# harp_expander_servo_driver_v1_1.net
KiCad netlist of a schematic drawn in EAGLE
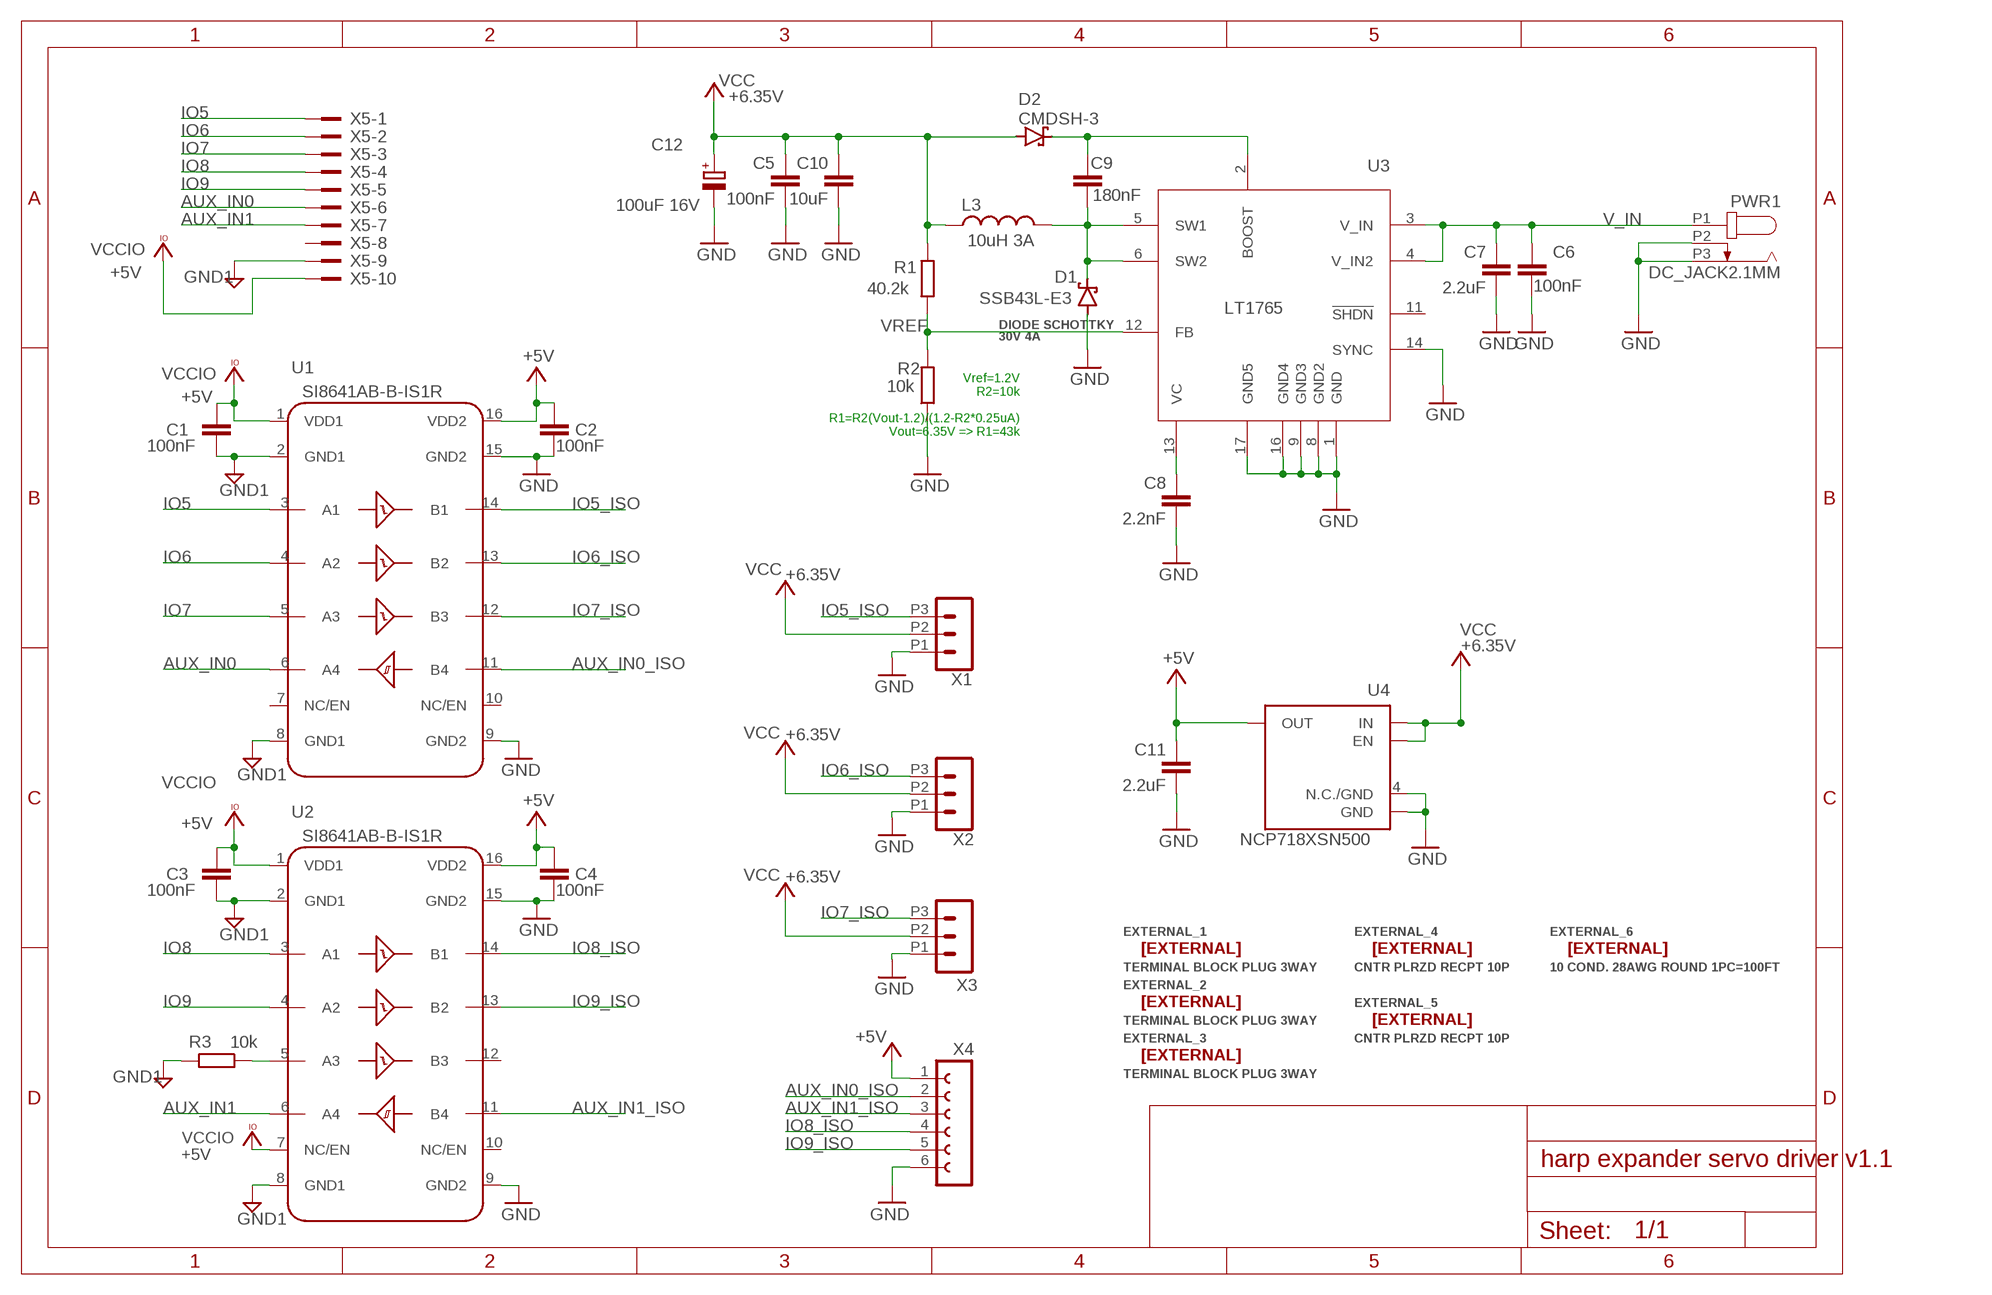
[diagram p0: schematic, sheet 1]

(export (version "E")
  (design (tool "Eeschema 10.0.6"))
  (components
    (comp (ref "C1")
      (value "100nF")
      (footprint "eagle-import:C0402")
      (fields (field (name "MPN") "CGA2B3X7R1H104K050BB"))
      (libsource (lib "eagle-import") (part "C-EUC0402"))
    )
    (comp (ref "C2")
      (value "100nF")
      (footprint "eagle-import:C0402")
      (fields (field (name "MPN") "CGA2B3X7R1H104K050BB"))
      (libsource (lib "eagle-import") (part "C-EUC0402"))
    )
    (comp (ref "C3")
      (value "100nF")
      (footprint "eagle-import:C0402")
      (fields (field (name "MPN") "CGA2B3X7R1H104K050BB"))
      (libsource (lib "eagle-import") (part "C-EUC0402"))
    )
    (comp (ref "C4")
      (value "100nF")
      (footprint "eagle-import:C0402")
      (fields (field (name "MPN") "CGA2B3X7R1H104K050BB"))
      (libsource (lib "eagle-import") (part "C-EUC0402"))
    )
    (comp (ref "C5")
      (value "100nF")
      (footprint "eagle-import:C0402")
      (fields (field (name "MPN") "CGA2B3X7R1H104K050BB"))
      (libsource (lib "eagle-import") (part "C-EUC0402"))
    )
    (comp (ref "C6")
      (value "100nF")
      (footprint "eagle-import:C0402")
      (fields (field (name "MPN") "CGA2B3X7R1H104K050BB"))
      (libsource (lib "eagle-import") (part "C-EUC0402"))
    )
    (comp (ref "C7")
      (value "2.2uF")
      (footprint "eagle-import:C0603")
      (fields (field (name "MPN") "GRM188R61E225MA12D"))
      (libsource (lib "eagle-import") (part "C-EUC0603"))
    )
    (comp (ref "C8")
      (value "2.2nF")
      (footprint "eagle-import:C0402")
      (fields (field (name "MPN") "CL05B222JB5NNNC"))
      (libsource (lib "eagle-import") (part "C-EUC0402"))
    )
    (comp (ref "C9")
      (value "180nF")
      (footprint "eagle-import:C0603")
      (fields (field (name "MPN") "GCG188R91H184KA01D"))
      (libsource (lib "eagle-import") (part "C-EUC0603"))
    )
    (comp (ref "C10")
      (value "10uF")
      (footprint "eagle-import:C0603")
      (fields (field (name "MPN") "EMK107BBJ106MA-T"))
      (libsource (lib "eagle-import") (part "C-EUC0603"))
    )
    (comp (ref "C11")
      (value "2.2uF")
      (footprint "eagle-import:C0603")
      (fields (field (name "MPN") "GRM188R61E225MA12D"))
      (libsource (lib "eagle-import") (part "C-EUC0603"))
    )
    (comp (ref "C12")
      (value "100uF 16V")
      (footprint "eagle-import:CT7343")
      (fields (field (name "MPN") "T491D107K016AT7280"))
      (libsource (lib "eagle-import") (part "CPOL-EUCT7343"))
    )
    (comp (ref "D1")
      (value "SSB43L-E3")
      (footprint "eagle-import:SMB")
      (fields (field (name "MPN") "SSB43L-E3/52T"))
      (libsource (lib "eagle-import") (part "MBRS130LT3"))
    )
    (comp (ref "D2")
      (value "CMDSH-3")
      (footprint "eagle-import:SOD323-R")
      (libsource (lib "eagle-import") (part "SCHOTTKY-DIODESOD323"))
    )
    (comp (ref "EXTERNAL_1")
      (value "TERMINAL BLOCK PLUG 3WAY")
      (footprint "eagle-import:-")
      (fields (field (name "MPN") "691361100003") (field (name "TYPE") "-"))
      (libsource (lib "eagle-import") (part "EXTERNAL"))
    )
    (comp (ref "EXTERNAL_2")
      (value "TERMINAL BLOCK PLUG 3WAY")
      (footprint "eagle-import:-")
      (fields (field (name "MPN") "691361100003") (field (name "TYPE") "-"))
      (libsource (lib "eagle-import") (part "EXTERNAL"))
    )
    (comp (ref "EXTERNAL_3")
      (value "TERMINAL BLOCK PLUG 3WAY")
      (footprint "eagle-import:-")
      (fields (field (name "MPN") "691361100003") (field (name "TYPE") "-"))
      (libsource (lib "eagle-import") (part "EXTERNAL"))
    )
    (comp (ref "EXTERNAL_4")
      (value "CNTR PLRZD RECPT 10P")
      (footprint "eagle-import:-")
      (fields (field (name "MPN") "1658621-1") (field (name "TYPE") "-"))
      (libsource (lib "eagle-import") (part "EXTERNAL"))
    )
    (comp (ref "EXTERNAL_5")
      (value "CNTR PLRZD RECPT 10P")
      (footprint "eagle-import:-")
      (fields (field (name "MPN") "1658621-1") (field (name "TYPE") "-"))
      (libsource (lib "eagle-import") (part "EXTERNAL"))
    )
    (comp (ref "EXTERNAL_6")
      (value "10 COND. 28AWG ROUND 1PC=100FT")
      (footprint "eagle-import:-")
      (fields (field (name "MPN") "3365/10 100") (field (name "TYPE") "-"))
      (libsource (lib "eagle-import") (part "EXTERNAL"))
    )
    (comp (ref "L3")
      (value "10uH 3A")
      (footprint "eagle-import:L_IHLP_PADS")
      (fields (field (name "MPN") "IHLP2525CZER100M01"))
      (libsource (lib "eagle-import") (part "L_IHLP2525CZER100M01"))
    )
    (comp (ref "PWR1")
      (value "DC_JACK2.1MM")
      (footprint "eagle-import:DC_POWER_INPUT_2.1MM")
      (fields (field (name "MPN") "163-179PH-EX"))
      (libsource (lib "eagle-import") (part "DC_JACK2.1MM"))
    )
    (comp (ref "R1")
      (value "40.2k")
      (footprint "eagle-import:R0402")
      (fields (field (name "MPN") "RC0402FR-0740K2L"))
      (libsource (lib "eagle-import") (part "R-EU_R0402"))
    )
    (comp (ref "R2")
      (value "10k")
      (footprint "eagle-import:R0402")
      (fields (field (name "MPN") "CRCW040210K0FKEDC"))
      (libsource (lib "eagle-import") (part "R-EU_R0402"))
    )
    (comp (ref "R3")
      (value "10k")
      (footprint "eagle-import:R0402")
      (fields (field (name "MPN") "CRCW040210K0FKEDC"))
      (libsource (lib "eagle-import") (part "R-EU_R0402"))
    )
    (comp (ref "U1")
      (value "SI8641AB-B-IS1R")
      (footprint "eagle-import:SO16W")
      (libsource (lib "eagle-import") (part "SI8641ABW"))
    )
    (comp (ref "U2")
      (value "SI8641AB-B-IS1R")
      (footprint "eagle-import:SO16W")
      (libsource (lib "eagle-import") (part "SI8641ABW"))
    )
    (comp (ref "U3")
      (value "LT1765")
      (footprint "eagle-import:TSSOP16")
      (fields (field (name "MPN") "LT1765EFE#TRPBF"))
      (libsource (lib "eagle-import") (part "LT1765"))
    )
    (comp (ref "U4")
      (value "NCP718XSN500")
      (footprint "eagle-import:SOT23-5")
      (fields (field (name "MPN") "NCP718BSN500T1G"))
      (libsource (lib "eagle-import") (part "NCP718XSN500"))
    )
    (comp (ref "X1")
      (value "CON_3.5MM_1X3")
      (footprint "eagle-import:CON_3.5MM_1X3")
      (fields (field (name "MPN") "691322110003"))
      (libsource (lib "eagle-import") (part "CON_3.5MM_1X3"))
    )
    (comp (ref "X2")
      (value "CON_3.5MM_1X3")
      (footprint "eagle-import:CON_3.5MM_1X3")
      (fields (field (name "MPN") "691322110003"))
      (libsource (lib "eagle-import") (part "CON_3.5MM_1X3"))
    )
    (comp (ref "X3")
      (value "CON_3.5MM_1X3")
      (footprint "eagle-import:CON_3.5MM_1X3")
      (fields (field (name "MPN") "691322110003"))
      (libsource (lib "eagle-import") (part "CON_3.5MM_1X3"))
    )
    (comp (ref "X4")
      (value "aux_header")
      (footprint "eagle-import:FE06")
      (fields (field (name "MPN") "n.a."))
      (libsource (lib "eagle-import") (part "FE06-1"))
    )
    (comp (ref "X5")
      (value "IDC 10WAY STRAIGHT")
      (footprint "eagle-import:PAK100_2500-10")
      (fields
        (field (name "MF") "3M")
        (field (name "MPN") "2510-6002UB")
        (field (name "DIGIKEY_PN") "S9169-ND")
        (field (name "MF_1") "-")
        (field (name "MPN_1") "SBH11-PBPC-D05-ST-BK")
        (field (name "OC_FARNELL") "-")
        (field (name "OC_NEWARK") "-")
        (field (name "TYPE") "TH")
      )
      (libsource (lib "eagle-import") (part "2510-"))
    )
  )
  (nets
    (net (code "1") (name "+5V") (class "Default")
      (node (ref "C11") (pin "1") (pinfunction "1_1") (pintype "passive"))
      (node (ref "C2") (pin "1") (pinfunction "1_1") (pintype "passive"))
      (node (ref "C4") (pin "1") (pinfunction "1_1") (pintype "passive"))
      (node (ref "U1") (pin "16") (pinfunction "VDD2_16") (pintype "bidirectional"))
      (node (ref "U2") (pin "16") (pinfunction "VDD2_16") (pintype "bidirectional"))
      (node (ref "U4") (pin "5") (pinfunction "OUT_5") (pintype "passive"))
      (node (ref "X4") (pin "1") (pinfunction "1_1") (pintype "passive"))
    )
    (net (code "2") (name "/AUX_IN0") (class "Default")
      (node (ref "U1") (pin "6") (pinfunction "A4_6") (pintype "bidirectional"))
      (node (ref "X5") (pin "6") (pinfunction "KL_6") (pintype "passive"))
    )
    (net (code "3") (name "/AUX_IN0_ISO") (class "Default")
      (node (ref "U1") (pin "11") (pinfunction "B4_11") (pintype "bidirectional"))
      (node (ref "X4") (pin "2") (pinfunction "2_2") (pintype "passive"))
    )
    (net (code "4") (name "/AUX_IN1") (class "Default")
      (node (ref "U2") (pin "6") (pinfunction "A4_6") (pintype "bidirectional"))
      (node (ref "X5") (pin "7") (pinfunction "KL_7") (pintype "passive"))
    )
    (net (code "5") (name "/AUX_IN1_ISO") (class "Default")
      (node (ref "U2") (pin "11") (pinfunction "B4_11") (pintype "bidirectional"))
      (node (ref "X4") (pin "3") (pinfunction "3_3") (pintype "passive"))
    )
    (net (code "6") (name "/IO5") (class "Default")
      (node (ref "U1") (pin "3") (pinfunction "A1_3") (pintype "bidirectional"))
      (node (ref "X5") (pin "1") (pinfunction "KL_1") (pintype "passive"))
    )
    (net (code "7") (name "/IO5_ISO") (class "Default")
      (node (ref "U1") (pin "14") (pinfunction "B1_14") (pintype "bidirectional"))
      (node (ref "X1") (pin "P3") (pinfunction "3_P3") (pintype "passive"))
    )
    (net (code "8") (name "/IO6") (class "Default")
      (node (ref "U1") (pin "4") (pinfunction "A2_4") (pintype "bidirectional"))
      (node (ref "X5") (pin "2") (pinfunction "KL_2") (pintype "passive"))
    )
    (net (code "9") (name "/IO6_ISO") (class "Default")
      (node (ref "U1") (pin "13") (pinfunction "B2_13") (pintype "bidirectional"))
      (node (ref "X2") (pin "P3") (pinfunction "3_P3") (pintype "passive"))
    )
    (net (code "10") (name "/IO7") (class "Default")
      (node (ref "U1") (pin "5") (pinfunction "A3_5") (pintype "bidirectional"))
      (node (ref "X5") (pin "3") (pinfunction "KL_3") (pintype "passive"))
    )
    (net (code "11") (name "/IO7_ISO") (class "Default")
      (node (ref "U1") (pin "12") (pinfunction "B3_12") (pintype "bidirectional"))
      (node (ref "X3") (pin "P3") (pinfunction "3_P3") (pintype "passive"))
    )
    (net (code "12") (name "/IO8") (class "Default")
      (node (ref "U2") (pin "3") (pinfunction "A1_3") (pintype "bidirectional"))
      (node (ref "X5") (pin "4") (pinfunction "KL_4") (pintype "passive"))
    )
    (net (code "13") (name "/IO8_ISO") (class "Default")
      (node (ref "U2") (pin "14") (pinfunction "B1_14") (pintype "bidirectional"))
      (node (ref "X4") (pin "4") (pinfunction "4_4") (pintype "passive"))
    )
    (net (code "14") (name "/IO9") (class "Default")
      (node (ref "U2") (pin "4") (pinfunction "A2_4") (pintype "bidirectional"))
      (node (ref "X5") (pin "5") (pinfunction "KL_5") (pintype "passive"))
    )
    (net (code "15") (name "/IO9_ISO") (class "Default")
      (node (ref "U2") (pin "13") (pinfunction "B2_13") (pintype "bidirectional"))
      (node (ref "X4") (pin "5") (pinfunction "5_5") (pintype "passive"))
    )
    (net (code "16") (name "/VREF") (class "Default")
      (node (ref "R1") (pin "1") (pinfunction "1_1") (pintype "passive"))
      (node (ref "R2") (pin "2") (pinfunction "2_2") (pintype "passive"))
      (node (ref "U3") (pin "12") (pinfunction "FB_12") (pintype "passive"))
    )
    (net (code "17") (name "/V_IN") (class "Default")
      (node (ref "C6") (pin "1") (pinfunction "1_1") (pintype "passive"))
      (node (ref "C7") (pin "1") (pinfunction "1_1") (pintype "passive"))
      (node (ref "PWR1") (pin "P1") (pinfunction "1_P1") (pintype "passive"))
      (node (ref "U3") (pin "3") (pinfunction "V_IN_3") (pintype "passive"))
      (node (ref "U3") (pin "4") (pinfunction "V_IN2_4") (pintype "passive"))
    )
    (net (code "18") (name "GND") (class "Default")
      (node (ref "C10") (pin "2") (pinfunction "2_2") (pintype "passive"))
      (node (ref "C11") (pin "2") (pinfunction "2_2") (pintype "passive"))
      (node (ref "C12") (pin "-") (pinfunction "-_-") (pintype "passive"))
      (node (ref "C2") (pin "2") (pinfunction "2_2") (pintype "passive"))
      (node (ref "C4") (pin "2") (pinfunction "2_2") (pintype "passive"))
      (node (ref "C5") (pin "2") (pinfunction "2_2") (pintype "passive"))
      (node (ref "C6") (pin "2") (pinfunction "2_2") (pintype "passive"))
      (node (ref "C7") (pin "2") (pinfunction "2_2") (pintype "passive"))
      (node (ref "C8") (pin "2") (pinfunction "2_2") (pintype "passive"))
      (node (ref "D1") (pin "A") (pinfunction "A_A") (pintype "passive"))
      (node (ref "PWR1") (pin "P2") (pinfunction "2_P2") (pintype "passive"))
      (node (ref "PWR1") (pin "P3") (pinfunction "3_P3") (pintype "passive"))
      (node (ref "R2") (pin "1") (pinfunction "1_1") (pintype "passive"))
      (node (ref "U1") (pin "15") (pinfunction "GND2_15") (pintype "bidirectional"))
      (node (ref "U1") (pin "9") (pinfunction "GND2_9") (pintype "bidirectional"))
      (node (ref "U2") (pin "15") (pinfunction "GND2_15") (pintype "bidirectional"))
      (node (ref "U2") (pin "9") (pinfunction "GND2_9") (pintype "bidirectional"))
      (node (ref "U3") (pin "1") (pinfunction "GND_1") (pintype "passive"))
      (node (ref "U3") (pin "14") (pinfunction "SYNC_14") (pintype "passive"))
      (node (ref "U3") (pin "16") (pinfunction "GND4_16") (pintype "passive"))
      (node (ref "U3") (pin "17") (pinfunction "GND5_17") (pintype "passive"))
      (node (ref "U3") (pin "8") (pinfunction "GND2_8") (pintype "passive"))
      (node (ref "U3") (pin "9") (pinfunction "GND3_9") (pintype "passive"))
      (node (ref "U4") (pin "2") (pinfunction "GND_2") (pintype "passive"))
      (node (ref "U4") (pin "4") (pinfunction "N.C./GND_4") (pintype "passive"))
      (node (ref "X1") (pin "P1") (pinfunction "1_P1") (pintype "passive"))
      (node (ref "X2") (pin "P1") (pinfunction "1_P1") (pintype "passive"))
      (node (ref "X3") (pin "P1") (pinfunction "1_P1") (pintype "passive"))
      (node (ref "X4") (pin "6") (pinfunction "6_6") (pintype "passive"))
    )
    (net (code "19") (name "GND1") (class "Default")
      (node (ref "C1") (pin "2") (pinfunction "2_2") (pintype "passive"))
      (node (ref "C3") (pin "2") (pinfunction "2_2") (pintype "passive"))
      (node (ref "R3") (pin "2") (pinfunction "2_2") (pintype "passive"))
      (node (ref "U1") (pin "2") (pinfunction "GND1_2") (pintype "bidirectional"))
      (node (ref "U1") (pin "8") (pinfunction "GND1_8") (pintype "bidirectional"))
      (node (ref "U2") (pin "2") (pinfunction "GND1_2") (pintype "bidirectional"))
      (node (ref "U2") (pin "8") (pinfunction "GND1_8") (pintype "bidirectional"))
      (node (ref "X5") (pin "9") (pinfunction "KL_9") (pintype "passive"))
    )
    (net (code "20") (name "Net-(U2-A3)") (class "Default")
      (node (ref "R3") (pin "1") (pinfunction "1_1") (pintype "passive"))
      (node (ref "U2") (pin "5") (pinfunction "A3_5") (pintype "bidirectional"))
    )
    (net (code "21") (name "Net-(U3-BOOST)") (class "Default")
      (node (ref "C9") (pin "1") (pinfunction "1_1") (pintype "passive"))
      (node (ref "D2") (pin "C") (pinfunction "C_C") (pintype "passive"))
      (node (ref "U3") (pin "2") (pinfunction "BOOST_2") (pintype "passive"))
    )
    (net (code "22") (name "Net-(U3-SW1)") (class "Default")
      (node (ref "C9") (pin "2") (pinfunction "2_2") (pintype "passive"))
      (node (ref "D1") (pin "C") (pinfunction "C_C") (pintype "passive"))
      (node (ref "L3") (pin "2") (pinfunction "2_2") (pintype "passive"))
      (node (ref "U3") (pin "5") (pinfunction "SW1_5") (pintype "passive"))
      (node (ref "U3") (pin "6") (pinfunction "SW2_6") (pintype "passive"))
    )
    (net (code "23") (name "Net-(U3-VC)") (class "Default")
      (node (ref "C8") (pin "1") (pinfunction "1_1") (pintype "passive"))
      (node (ref "U3") (pin "13") (pinfunction "VC_13") (pintype "passive"))
    )
    (net (code "24") (name "VCC") (class "Default")
      (node (ref "C10") (pin "1") (pinfunction "1_1") (pintype "passive"))
      (node (ref "C12") (pin "+") (pinfunction "+_+") (pintype "passive"))
      (node (ref "C5") (pin "1") (pinfunction "1_1") (pintype "passive"))
      (node (ref "D2") (pin "A") (pinfunction "A_A") (pintype "passive"))
      (node (ref "L3") (pin "1") (pinfunction "1_1") (pintype "passive"))
      (node (ref "R1") (pin "2") (pinfunction "2_2") (pintype "passive"))
      (node (ref "U4") (pin "1") (pinfunction "IN_1") (pintype "passive"))
      (node (ref "U4") (pin "3") (pinfunction "EN_3") (pintype "passive"))
      (node (ref "X1") (pin "P2") (pinfunction "2_P2") (pintype "passive"))
      (node (ref "X2") (pin "P2") (pinfunction "2_P2") (pintype "passive"))
      (node (ref "X3") (pin "P2") (pinfunction "2_P2") (pintype "passive"))
    )
    (net (code "25") (name "VCCIO") (class "Default")
      (node (ref "C1") (pin "1") (pinfunction "1_1") (pintype "passive"))
      (node (ref "C3") (pin "1") (pinfunction "1_1") (pintype "passive"))
      (node (ref "U1") (pin "1") (pinfunction "VDD1_1") (pintype "bidirectional"))
      (node (ref "U2") (pin "1") (pinfunction "VDD1_1") (pintype "bidirectional"))
      (node (ref "U2") (pin "7") (pinfunction "NC/EN_7") (pintype "bidirectional"))
      (node (ref "X5") (pin "10") (pinfunction "KL_10") (pintype "passive"))
    )
    (net (code "26") (name "unconnected-(U1-NC{slash}EN-Pad7)") (class "Default")
      (node (ref "U1") (pin "7") (pinfunction "NC/EN_7") (pintype "bidirectional"))
    )
    (net (code "27") (name "unconnected-(U1-NC{slash}EN-Pad10)") (class "Default")
      (node (ref "U1") (pin "10") (pinfunction "NC/EN_10") (pintype "bidirectional"))
    )
    (net (code "28") (name "unconnected-(U2-B3-Pad12)") (class "Default")
      (node (ref "U2") (pin "12") (pinfunction "B3_12") (pintype "bidirectional"))
    )
    (net (code "29") (name "unconnected-(U2-NC{slash}EN-Pad10)") (class "Default")
      (node (ref "U2") (pin "10") (pinfunction "NC/EN_10") (pintype "bidirectional"))
    )
    (net (code "30") (name "unconnected-(U3-NC7-Pad7)") (class "Default")
      (node (ref "U3") (pin "7") (pinfunction "NC7_7") (pintype "no_connect"))
    )
    (net (code "31") (name "unconnected-(U3-NC10-Pad10)") (class "Default")
      (node (ref "U3") (pin "10") (pinfunction "NC10_10") (pintype "no_connect"))
    )
    (net (code "32") (name "unconnected-(U3-NC15-Pad15)") (class "Default")
      (node (ref "U3") (pin "15") (pinfunction "NC15_15") (pintype "no_connect"))
    )
    (net (code "33") (name "unconnected-(U3-~{SHDN}-Pad11)") (class "Default")
      (node (ref "U3") (pin "11") (pinfunction "~{SHDN}_11") (pintype "passive"))
    )
    (net (code "34") (name "unconnected-(X5I-KL-Pad8)") (class "Default")
      (node (ref "X5") (pin "8") (pinfunction "KL_8") (pintype "passive"))
    )
  )
)
